# IR_tester_light.net
KiCad netlist of a schematic drawn in EAGLE
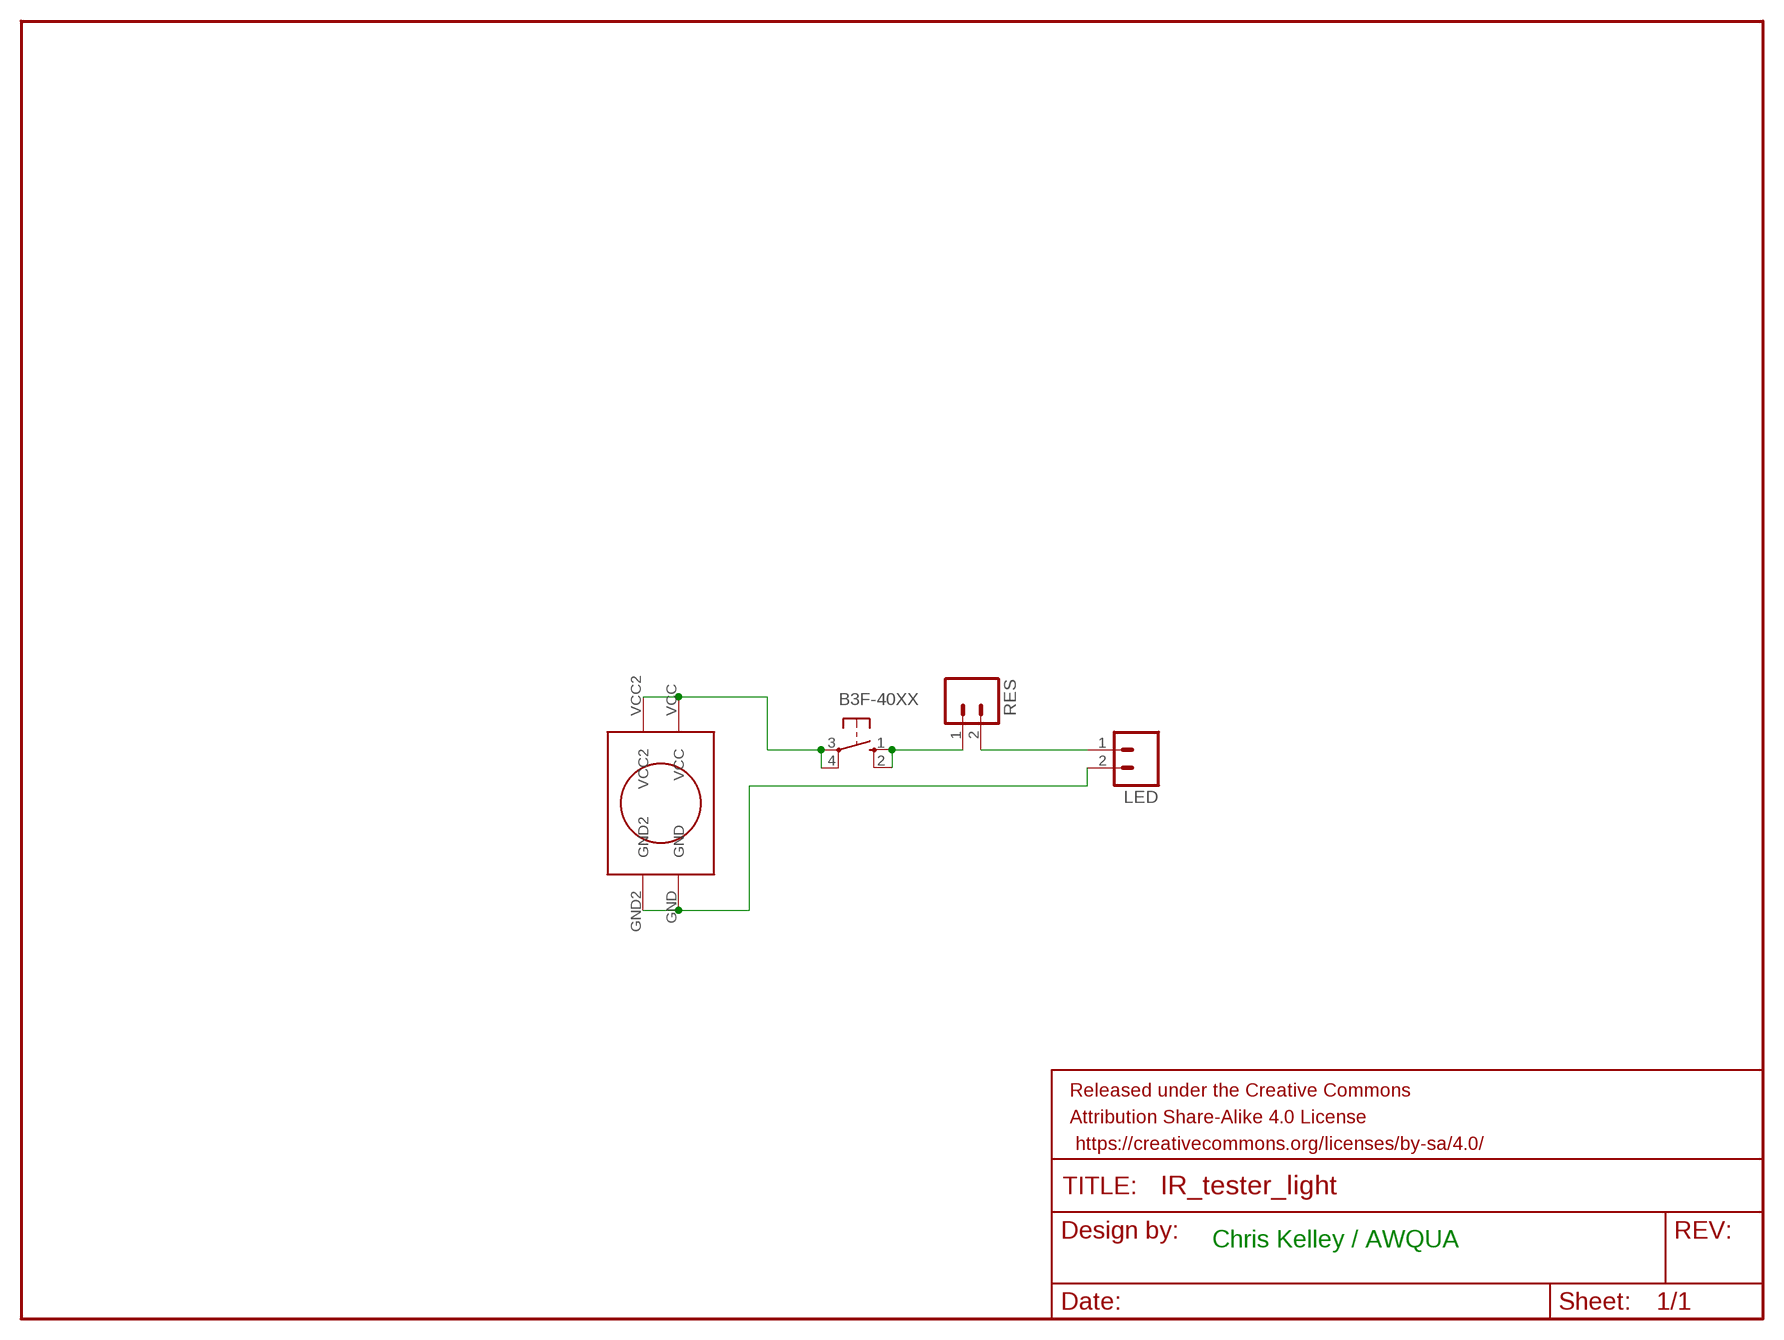
[diagram p0: schematic, sheet 1]

(export (version "E")
  (design (tool "Eeschema 10.0.6"))
  (components
    (comp (ref "B3F-40XX")
      (value "40-XX")
      (footprint "eagle-import:B3F-40XX")
      (fields (field (name "MF") "OMRON COMPONENTS USA") (field (name "MPN") "B3F-4000"))
      (libsource (lib "eagle-import") (part "40-XX"))
    )
    (comp (ref "FRAME1")
      (value "FRAME-LETTER")
      (footprint "eagle-import:CREATIVE_COMMONS")
      (libsource (lib "eagle-import") (part "FRAME-LETTER"))
    )
    (comp (ref "LED")
      (value "M02PTH")
      (footprint "eagle-import:1X02")
      (libsource (lib "eagle-import") (part "M02PTH"))
    )
    (comp (ref "RES")
      (value "M02PTH")
      (footprint "eagle-import:1X02")
      (libsource (lib "eagle-import") (part "M02PTH"))
    )
    (comp (ref "U$1")
      (value "CR1632-KEYSTYONE-3013")
      (footprint "eagle-import:CR1632-KEYSTYONE-3013")
      (libsource (lib "eagle-import") (part "CR1632-KEYSTYONE-3013"))
    )
  )
  (nets
    (net (code "1") (name "Net-(B3F-40XX-P)") (class "Default")
      (node (ref "B3F-40XX") (pin "3") (pinfunction "P_3") (pintype "passive"))
      (node (ref "B3F-40XX") (pin "4") (pinfunction "P1_4") (pintype "passive"))
      (node (ref "U$1") (pin "VCC") (pinfunction "VCC_VCC") (pintype "bidirectional"))
      (node (ref "U$1") (pin "VCC2") (pinfunction "VCC2_VCC2") (pintype "bidirectional"))
    )
    (net (code "2") (name "Net-(B3F-40XX-S)") (class "Default")
      (node (ref "B3F-40XX") (pin "1") (pinfunction "S_1") (pintype "passive"))
      (node (ref "B3F-40XX") (pin "2") (pinfunction "S1_2") (pintype "passive"))
      (node (ref "RES") (pin "1") (pinfunction "1_1") (pintype "passive"))
    )
    (net (code "3") (name "Net-(LED-Pad1)") (class "Default")
      (node (ref "LED") (pin "1") (pinfunction "1_1") (pintype "passive"))
      (node (ref "RES") (pin "2") (pinfunction "2_2") (pintype "passive"))
    )
    (net (code "4") (name "Net-(LED-Pad2)") (class "Default")
      (node (ref "LED") (pin "2") (pinfunction "2_2") (pintype "passive"))
      (node (ref "U$1") (pin "GND") (pinfunction "GND_GND") (pintype "bidirectional"))
      (node (ref "U$1") (pin "GND2") (pinfunction "GND2_GND2") (pintype "bidirectional"))
    )
  )
)
